# ECE_388_Schematic_v3.net
KiCad netlist of a schematic drawn in EAGLE
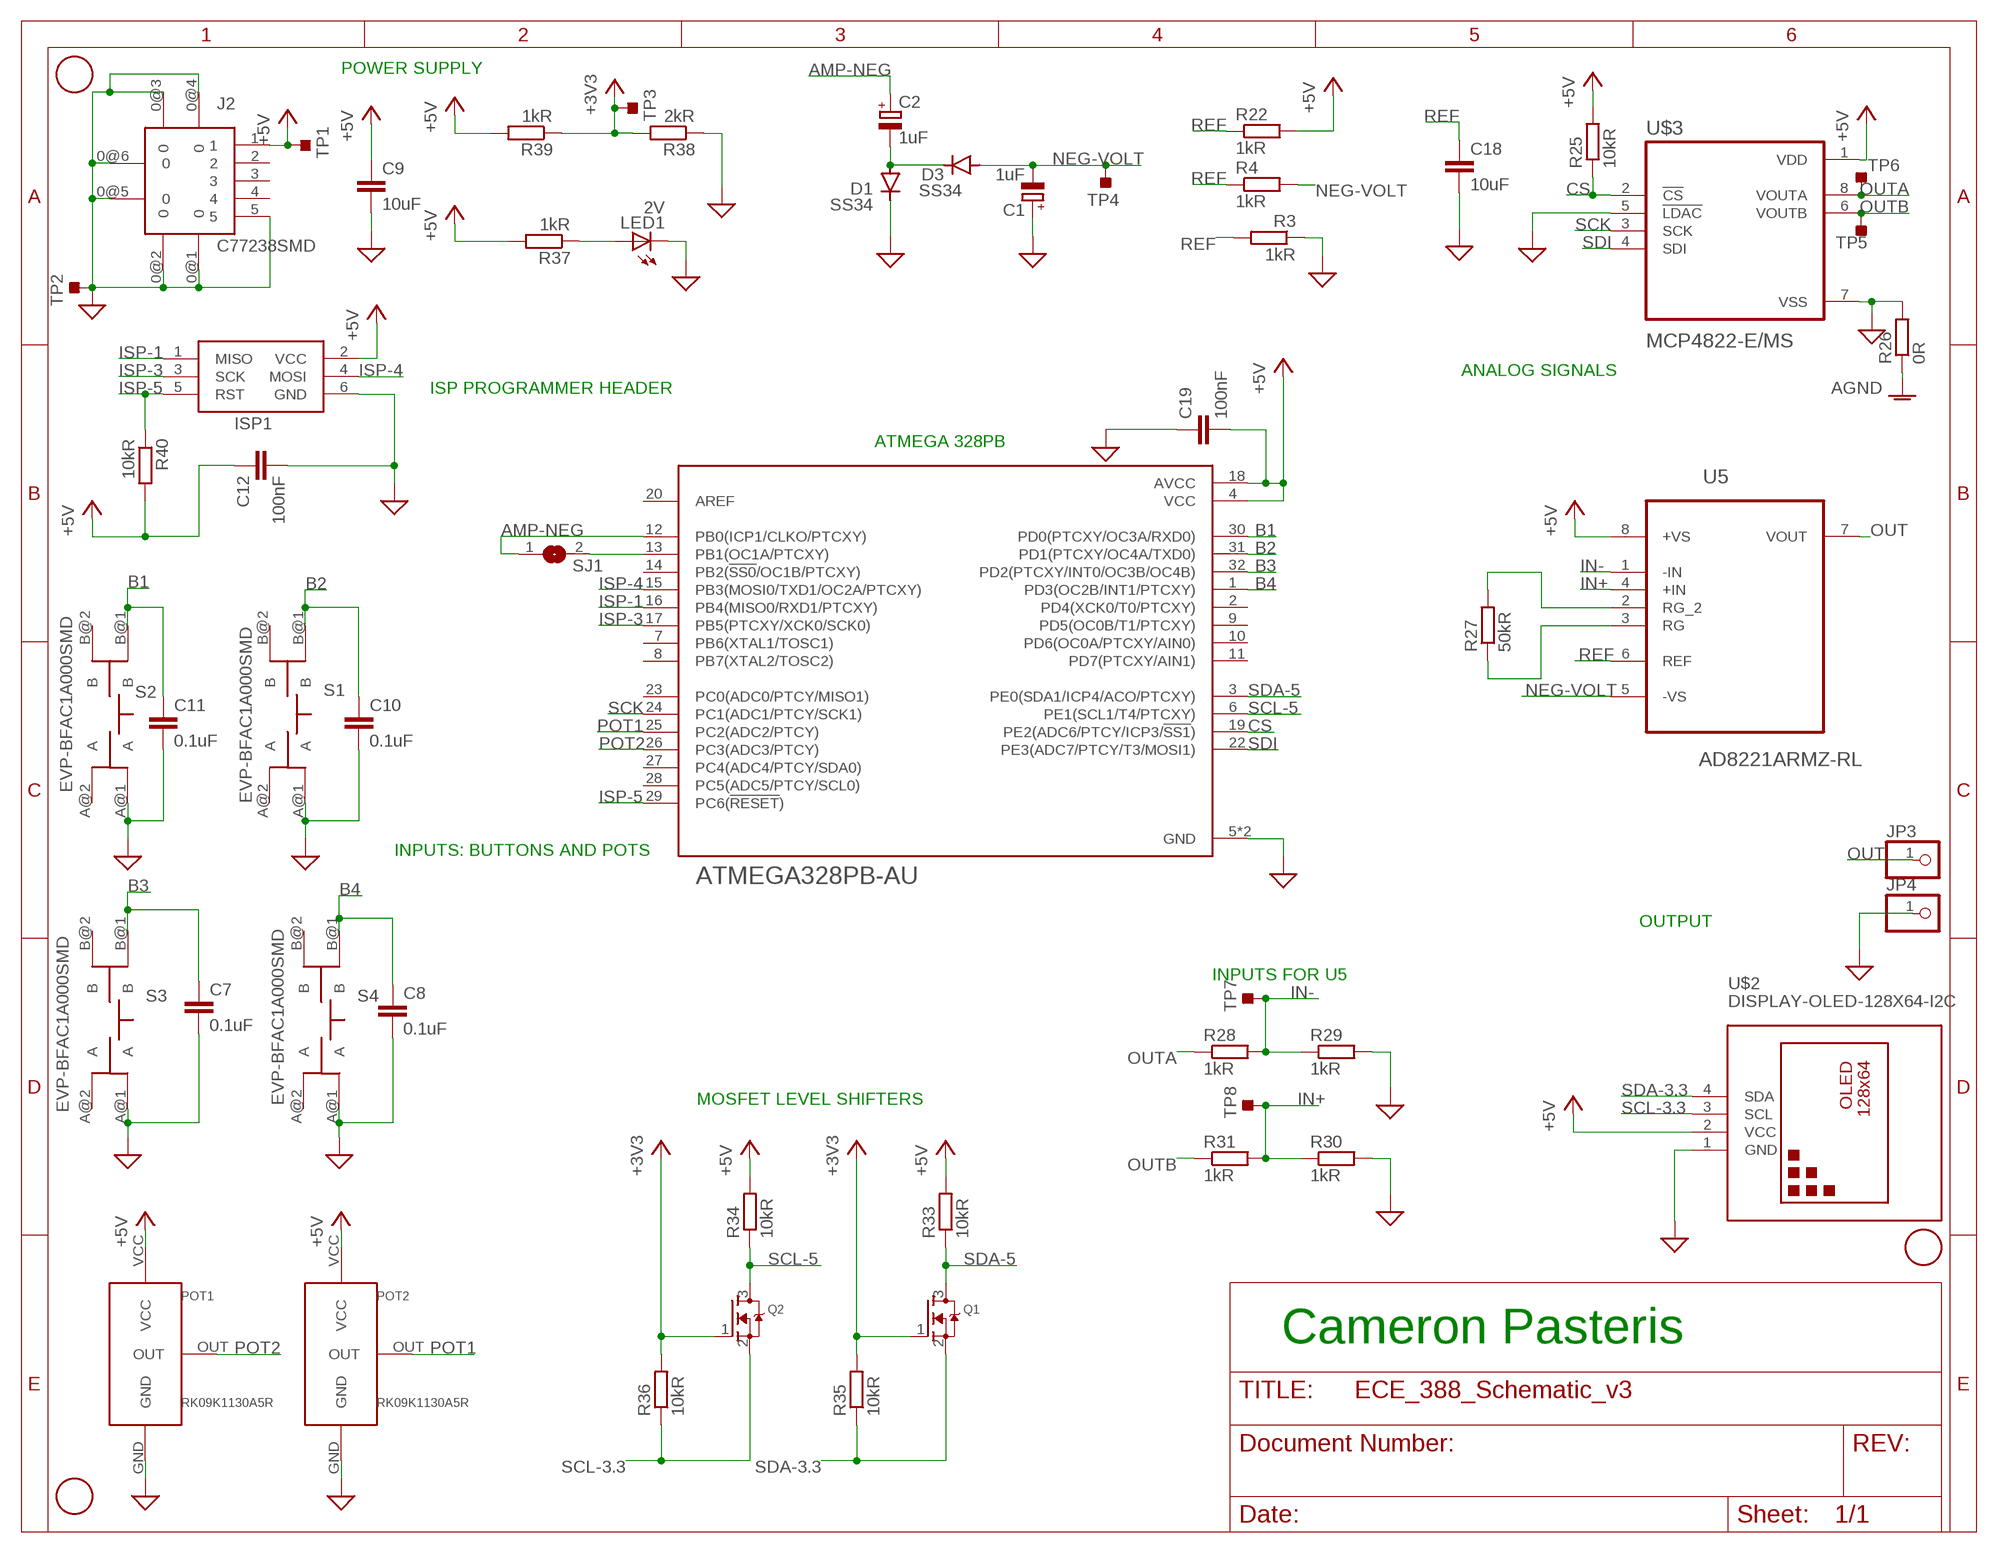
[diagram p0: schematic, sheet 1]

(export (version "E")
  (design (tool "Eeschema 10.0.6"))
  (components
    (comp (ref "C1")
      (value "1uF")
      (footprint "eagle-import:E2,5-6E")
      (libsource (lib "eagle-import") (part "CPOL-EUE2,5-6E"))
    )
    (comp (ref "C2")
      (value "1uF")
      (footprint "eagle-import:E2,5-6E")
      (libsource (lib "eagle-import") (part "CPOL-EUE2,5-6E"))
    )
    (comp (ref "C7")
      (value "0.1uF")
      (footprint "eagle-import:C0805")
      (libsource (lib "eagle-import") (part "C-EUC0805"))
    )
    (comp (ref "C8")
      (value "0.1uF")
      (footprint "eagle-import:C0805")
      (libsource (lib "eagle-import") (part "C-EUC0805"))
    )
    (comp (ref "C9")
      (value "10uF")
      (footprint "eagle-import:C0805")
      (libsource (lib "eagle-import") (part "C-EUC0805"))
    )
    (comp (ref "C10")
      (value "0.1uF")
      (footprint "eagle-import:C0805")
      (libsource (lib "eagle-import") (part "C-EUC0805"))
    )
    (comp (ref "C11")
      (value "0.1uF")
      (footprint "eagle-import:C0805")
      (libsource (lib "eagle-import") (part "C-EUC0805"))
    )
    (comp (ref "C12")
      (value "100nF")
      (footprint "eagle-import:C0805")
      (libsource (lib "eagle-import") (part "C-EUC0805"))
    )
    (comp (ref "C18")
      (value "10uF")
      (footprint "eagle-import:C0805")
      (libsource (lib "eagle-import") (part "C-EUC0805"))
    )
    (comp (ref "C19")
      (value "100nF")
      (footprint "eagle-import:C0805")
      (libsource (lib "eagle-import") (part "C-EUC0805"))
    )
    (comp (ref "D1")
      (value "SS34")
      (footprint "eagle-import:DO-214AC")
      (libsource (lib "eagle-import") (part "DIODE-DO-214AC"))
    )
    (comp (ref "D3")
      (value "SS34")
      (footprint "eagle-import:DO-214AC")
      (libsource (lib "eagle-import") (part "DIODE-DO-214AC"))
    )
    (comp (ref "F1")
      (value "FIDUCIAL")
      (footprint "eagle-import:FIDUCIAL_1MM")
      (libsource (lib "eagle-import") (part "FIDUCIAL"))
    )
    (comp (ref "F2")
      (value "FIDUCIAL")
      (footprint "eagle-import:FIDUCIAL_1MM")
      (libsource (lib "eagle-import") (part "FIDUCIAL"))
    )
    (comp (ref "F3")
      (value "FIDUCIAL")
      (footprint "eagle-import:FIDUCIAL_1MM")
      (libsource (lib "eagle-import") (part "FIDUCIAL"))
    )
    (comp (ref "ISP1")
      (value "AVRISP-6")
      (footprint "eagle-import:AVRISP")
      (libsource (lib "eagle-import") (part "AVRISP-6"))
    )
    (comp (ref "J2")
      (value "C77238SMD")
      (footprint "eagle-import:C77238")
      (libsource (lib "eagle-import") (part "C77238SMD"))
    )
    (comp (ref "JP3")
      (value "PINHD-1X1")
      (footprint "eagle-import:1X01")
      (libsource (lib "eagle-import") (part "PINHD-1X1"))
    )
    (comp (ref "JP4")
      (value "PINHD-1X1")
      (footprint "eagle-import:1X01")
      (libsource (lib "eagle-import") (part "PINHD-1X1"))
    )
    (comp (ref "LED1")
      (value "2V")
      (footprint "eagle-import:CHIP-LED0805")
      (libsource (lib "eagle-import") (part "LEDCHIP-LED0805"))
    )
    (comp (ref "POT1")
      (value "RK09K1130A5R")
      (footprint "eagle-import:RK09K1130A5R")
      (libsource (lib "eagle-import") (part "RK09K1130A5R"))
    )
    (comp (ref "POT2")
      (value "RK09K1130A5R")
      (footprint "eagle-import:RK09K1130A5R")
      (libsource (lib "eagle-import") (part "RK09K1130A5R"))
    )
    (comp (ref "Q1")
      (value "MOSFET-NREFLOW")
      (footprint "eagle-import:SOT23")
      (libsource (lib "eagle-import") (part "MOSFET-NREFLOW"))
    )
    (comp (ref "Q2")
      (value "MOSFET-NREFLOW")
      (footprint "eagle-import:SOT23")
      (libsource (lib "eagle-import") (part "MOSFET-NREFLOW"))
    )
    (comp (ref "R3")
      (value "1kR")
      (footprint "eagle-import:R0805")
      (libsource (lib "eagle-import") (part "R-EU_R0805"))
    )
    (comp (ref "R4")
      (value "1kR")
      (footprint "eagle-import:R0805")
      (libsource (lib "eagle-import") (part "R-EU_R0805"))
    )
    (comp (ref "R22")
      (value "1kR")
      (footprint "eagle-import:R0805")
      (libsource (lib "eagle-import") (part "R-EU_R0805"))
    )
    (comp (ref "R25")
      (value "10kR")
      (footprint "eagle-import:R0805")
      (libsource (lib "eagle-import") (part "R-EU_R0805"))
    )
    (comp (ref "R26")
      (value "0R")
      (footprint "eagle-import:R0805")
      (libsource (lib "eagle-import") (part "R-EU_R0805"))
    )
    (comp (ref "R27")
      (value "50kR")
      (footprint "eagle-import:R0805")
      (libsource (lib "eagle-import") (part "R-EU_R0805"))
    )
    (comp (ref "R28")
      (value "1kR")
      (footprint "eagle-import:R0805")
      (libsource (lib "eagle-import") (part "R-EU_R0805"))
    )
    (comp (ref "R29")
      (value "1kR")
      (footprint "eagle-import:R0805")
      (libsource (lib "eagle-import") (part "R-EU_R0805"))
    )
    (comp (ref "R30")
      (value "1kR")
      (footprint "eagle-import:R0805")
      (libsource (lib "eagle-import") (part "R-EU_R0805"))
    )
    (comp (ref "R31")
      (value "1kR")
      (footprint "eagle-import:R0805")
      (libsource (lib "eagle-import") (part "R-EU_R0805"))
    )
    (comp (ref "R33")
      (value "10kR")
      (footprint "eagle-import:R0805")
      (libsource (lib "eagle-import") (part "R-EU_R0805"))
    )
    (comp (ref "R34")
      (value "10kR")
      (footprint "eagle-import:R0805")
      (libsource (lib "eagle-import") (part "R-EU_R0805"))
    )
    (comp (ref "R35")
      (value "10kR")
      (footprint "eagle-import:R0805")
      (libsource (lib "eagle-import") (part "R-EU_R0805"))
    )
    (comp (ref "R36")
      (value "10kR")
      (footprint "eagle-import:R0805")
      (libsource (lib "eagle-import") (part "R-EU_R0805"))
    )
    (comp (ref "R37")
      (value "1kR")
      (footprint "eagle-import:R0805")
      (libsource (lib "eagle-import") (part "R-EU_R0805"))
    )
    (comp (ref "R38")
      (value "2kR")
      (footprint "eagle-import:R0805")
      (libsource (lib "eagle-import") (part "R-EU_R0805"))
    )
    (comp (ref "R39")
      (value "1kR")
      (footprint "eagle-import:R0805")
      (libsource (lib "eagle-import") (part "R-EU_R0805"))
    )
    (comp (ref "R40")
      (value "10kR")
      (footprint "eagle-import:R0805")
      (libsource (lib "eagle-import") (part "R-EU_R0805"))
    )
    (comp (ref "S1")
      (value "EVP-BFAC1A000SMD")
      (footprint "eagle-import:EVP-BFAC1A000")
      (libsource (lib "eagle-import") (part "EVP-BFAC1A000SMD"))
    )
    (comp (ref "S2")
      (value "EVP-BFAC1A000SMD")
      (footprint "eagle-import:EVP-BFAC1A000")
      (libsource (lib "eagle-import") (part "EVP-BFAC1A000SMD"))
    )
    (comp (ref "S3")
      (value "EVP-BFAC1A000SMD")
      (footprint "eagle-import:EVP-BFAC1A000")
      (libsource (lib "eagle-import") (part "EVP-BFAC1A000SMD"))
    )
    (comp (ref "S4")
      (value "EVP-BFAC1A000SMD")
      (footprint "eagle-import:EVP-BFAC1A000")
      (libsource (lib "eagle-import") (part "EVP-BFAC1A000SMD"))
    )
    (comp (ref "SJ1") (value "SJ") (footprint "eagle-import:SJ") (libsource (lib "eagle-import") (part "SJ")))
    (comp (ref "TP1")
      (value "TESTPOINT_TPS-PAD-036")
      (footprint "eagle-import:TESTPOINT_PAD-036")
      (libsource (lib "eagle-import") (part "TESTPOINT_TPS-PAD-036"))
    )
    (comp (ref "TP2")
      (value "TESTPOINT_TPS-PAD-036")
      (footprint "eagle-import:TESTPOINT_PAD-036")
      (libsource (lib "eagle-import") (part "TESTPOINT_TPS-PAD-036"))
    )
    (comp (ref "TP3")
      (value "TESTPOINT_TPS-PAD-036")
      (footprint "eagle-import:TESTPOINT_PAD-036")
      (libsource (lib "eagle-import") (part "TESTPOINT_TPS-PAD-036"))
    )
    (comp (ref "TP4")
      (value "TESTPOINT_TPS-PAD-036")
      (footprint "eagle-import:TESTPOINT_PAD-036")
      (libsource (lib "eagle-import") (part "TESTPOINT_TPS-PAD-036"))
    )
    (comp (ref "TP5")
      (value "TESTPOINT_TPS-PAD-036")
      (footprint "eagle-import:TESTPOINT_PAD-036")
      (libsource (lib "eagle-import") (part "TESTPOINT_TPS-PAD-036"))
    )
    (comp (ref "TP6")
      (value "TESTPOINT_TPS-PAD-036")
      (footprint "eagle-import:TESTPOINT_PAD-036")
      (libsource (lib "eagle-import") (part "TESTPOINT_TPS-PAD-036"))
    )
    (comp (ref "TP7")
      (value "TESTPOINT_TPS-PAD-036")
      (footprint "eagle-import:TESTPOINT_PAD-036")
      (libsource (lib "eagle-import") (part "TESTPOINT_TPS-PAD-036"))
    )
    (comp (ref "TP8")
      (value "TESTPOINT_TPS-PAD-036")
      (footprint "eagle-import:TESTPOINT_PAD-036")
      (libsource (lib "eagle-import") (part "TESTPOINT_TPS-PAD-036"))
    )
    (comp (ref "U$2")
      (value "DISPLAY-OLED-128X64-I2C")
      (footprint "eagle-import:DISPLAY-OLED-128X64-I2C")
      (libsource (lib "eagle-import") (part "DISPLAY-OLED-128X64-I2C"))
    )
    (comp (ref "U$3")
      (value "MCP4822-E/MS")
      (footprint "eagle-import:SOP65P490X110-8N")
      (fields (field (name "MF") "Microchip"))
      (libsource (lib "eagle-import") (part "MCP4822-E/MS"))
    )
    (comp (ref "U1")
      (value "ATMEGA328PB-AU")
      (footprint "eagle-import:QFP80P900X900X120-32N")
      (fields (field (name "MF") "Microchip Technology / Atmel"))
      (libsource (lib "eagle-import") (part "ATMEGA328PB-AU"))
    )
    (comp (ref "U5")
      (value "AD8221ARMZ-RL")
      (footprint "eagle-import:SOP65P490X110-8N")
      (fields (field (name "MF") "Analog Devices"))
      (libsource (lib "eagle-import") (part "AD8221ARMZ-RL"))
    )
  )
  (nets
    (net (code "1") (name "+3V3") (class "Default")
      (node (ref "Q1") (pin "1") (pinfunction "G_1") (pintype "bidirectional"))
      (node (ref "Q2") (pin "1") (pinfunction "G_1") (pintype "bidirectional"))
      (node (ref "R35") (pin "2") (pinfunction "2_2") (pintype "passive"))
      (node (ref "R36") (pin "2") (pinfunction "2_2") (pintype "passive"))
      (node (ref "R38") (pin "2") (pinfunction "2_2") (pintype "passive"))
      (node (ref "R39") (pin "1") (pinfunction "1_1") (pintype "passive"))
      (node (ref "TP3") (pin "1") (pinfunction "TP_1") (pintype "passive"))
    )
    (net (code "2") (name "+5V") (class "Default")
      (node (ref "C12") (pin "1") (pinfunction "1_1") (pintype "passive"))
      (node (ref "C19") (pin "2") (pinfunction "2_2") (pintype "passive"))
      (node (ref "C9") (pin "1") (pinfunction "1_1") (pintype "passive"))
      (node (ref "ISP1") (pin "2") (pinfunction "VCC_2") (pintype "power_in"))
      (node (ref "J2") (pin "1") (pinfunction "1_1") (pintype "power_in"))
      (node (ref "POT1") (pin "VCC") (pinfunction "VCC_VCC") (pintype "bidirectional"))
      (node (ref "POT2") (pin "VCC") (pinfunction "VCC_VCC") (pintype "bidirectional"))
      (node (ref "R22") (pin "2") (pinfunction "2_2") (pintype "passive"))
      (node (ref "R25") (pin "2") (pinfunction "2_2") (pintype "passive"))
      (node (ref "R33") (pin "2") (pinfunction "2_2") (pintype "passive"))
      (node (ref "R34") (pin "2") (pinfunction "2_2") (pintype "passive"))
      (node (ref "R37") (pin "2") (pinfunction "2_2") (pintype "passive"))
      (node (ref "R39") (pin "2") (pinfunction "2_2") (pintype "passive"))
      (node (ref "R40") (pin "2") (pinfunction "2_2") (pintype "passive"))
      (node (ref "TP1") (pin "1") (pinfunction "TP_1") (pintype "passive"))
      (node (ref "U$2") (pin "2") (pinfunction "VCC_2") (pintype "power_in"))
      (node (ref "U$3") (pin "1") (pinfunction "VDD_1") (pintype "power_in"))
      (node (ref "U1") (pin "18") (pinfunction "AVCC_18") (pintype "power_in"))
      (node (ref "U1") (pin "4") (pinfunction "VCC_4") (pintype "power_in"))
      (node (ref "U5") (pin "8") (pinfunction "+VS_8") (pintype "power_in"))
    )
    (net (code "3") (name "/AMP-NEG") (class "Default")
      (node (ref "C2") (pin "+") (pinfunction "+_+") (pintype "passive"))
      (node (ref "SJ1") (pin "1") (pinfunction "1_1") (pintype "passive"))
      (node (ref "U1") (pin "12") (pinfunction "PB0(ICP1/CLKO/PTCXY)_12") (pintype "bidirectional"))
    )
    (net (code "4") (name "/B1") (class "Default")
      (node (ref "C11") (pin "1") (pinfunction "1_1") (pintype "passive"))
      (node (ref "S2") (pin "B@1") (pinfunction "B_B@1") (pintype "bidirectional"))
      (node (ref "U1") (pin "30") (pinfunction "PD0(PTCXY/OC3A/RXD0)_30") (pintype "bidirectional"))
    )
    (net (code "5") (name "/B2") (class "Default")
      (node (ref "C10") (pin "1") (pinfunction "1_1") (pintype "passive"))
      (node (ref "S1") (pin "B@1") (pinfunction "B_B@1") (pintype "bidirectional"))
      (node (ref "U1") (pin "31") (pinfunction "PD1(PTCXY/OC4A/TXD0)_31") (pintype "bidirectional"))
    )
    (net (code "6") (name "/B3") (class "Default")
      (node (ref "C7") (pin "1") (pinfunction "1_1") (pintype "passive"))
      (node (ref "S3") (pin "B@1") (pinfunction "B_B@1") (pintype "bidirectional"))
      (node (ref "U1") (pin "32") (pinfunction "PD2(PTCXY/INT0/OC3B/OC4B)_32") (pintype "bidirectional"))
    )
    (net (code "7") (name "/B4") (class "Default")
      (node (ref "C8") (pin "1") (pinfunction "1_1") (pintype "passive"))
      (node (ref "S4") (pin "B@1") (pinfunction "B_B@1") (pintype "bidirectional"))
      (node (ref "U1") (pin "1") (pinfunction "PD3(OC2B/INT1/PTCXY)_1") (pintype "bidirectional"))
    )
    (net (code "8") (name "/CS") (class "Default")
      (node (ref "R25") (pin "1") (pinfunction "1_1") (pintype "passive"))
      (node (ref "U$3") (pin "2") (pinfunction "~{CS}_2") (pintype "input"))
      (node (ref "U1") (pin "19") (pinfunction "PE2(ADC6/PTCY/ICP3/~{SS1})_19") (pintype "bidirectional"))
    )
    (net (code "9") (name "/IN+") (class "Default")
      (node (ref "R30") (pin "1") (pinfunction "1_1") (pintype "passive"))
      (node (ref "R31") (pin "2") (pinfunction "2_2") (pintype "passive"))
      (node (ref "TP8") (pin "1") (pinfunction "TP_1") (pintype "passive"))
      (node (ref "U5") (pin "4") (pinfunction "+IN_4") (pintype "input"))
    )
    (net (code "10") (name "/IN-") (class "Default")
      (node (ref "R28") (pin "2") (pinfunction "2_2") (pintype "passive"))
      (node (ref "R29") (pin "1") (pinfunction "1_1") (pintype "passive"))
      (node (ref "TP7") (pin "1") (pinfunction "TP_1") (pintype "passive"))
      (node (ref "U5") (pin "1") (pinfunction "-IN_1") (pintype "input"))
    )
    (net (code "11") (name "/ISP-1") (class "Default")
      (node (ref "ISP1") (pin "1") (pinfunction "MISO_1") (pintype "input"))
      (node (ref "U1") (pin "16") (pinfunction "PB4(MISO0/RXD1/PTCXY)_16") (pintype "bidirectional"))
    )
    (net (code "12") (name "/ISP-3") (class "Default")
      (node (ref "ISP1") (pin "3") (pinfunction "SCK_3") (pintype "output"))
      (node (ref "U1") (pin "17") (pinfunction "PB5(PTCXY/XCK0/SCK0)_17") (pintype "bidirectional"))
    )
    (net (code "13") (name "/ISP-4") (class "Default")
      (node (ref "ISP1") (pin "4") (pinfunction "MOSI_4") (pintype "output"))
      (node (ref "U1") (pin "15") (pinfunction "PB3(MOSI0/TXD1/OC2A/PTCXY)_15") (pintype "bidirectional"))
    )
    (net (code "14") (name "/ISP-5") (class "Default")
      (node (ref "ISP1") (pin "5") (pinfunction "RST_5") (pintype "output"))
      (node (ref "R40") (pin "1") (pinfunction "1_1") (pintype "passive"))
      (node (ref "U1") (pin "29") (pinfunction "PC6(~{RESET})_29") (pintype "bidirectional"))
    )
    (net (code "15") (name "/NEG-VOLT") (class "Default")
      (node (ref "C1") (pin "-") (pinfunction "-_-") (pintype "passive"))
      (node (ref "D3") (pin "A") (pinfunction "A_A") (pintype "passive"))
      (node (ref "R4") (pin "2") (pinfunction "2_2") (pintype "passive"))
      (node (ref "TP4") (pin "1") (pinfunction "TP_1") (pintype "passive"))
      (node (ref "U5") (pin "5") (pinfunction "-VS_5") (pintype "power_in"))
    )
    (net (code "16") (name "/OUT") (class "Default")
      (node (ref "JP3") (pin "1") (pinfunction "1_1") (pintype "passive"))
      (node (ref "U5") (pin "7") (pinfunction "VOUT_7") (pintype "output"))
    )
    (net (code "17") (name "/OUTA") (class "Default")
      (node (ref "R28") (pin "1") (pinfunction "1_1") (pintype "passive"))
      (node (ref "TP6") (pin "1") (pinfunction "TP_1") (pintype "passive"))
      (node (ref "U$3") (pin "8") (pinfunction "VOUTA_8") (pintype "output"))
    )
    (net (code "18") (name "/OUTB") (class "Default")
      (node (ref "R31") (pin "1") (pinfunction "1_1") (pintype "passive"))
      (node (ref "TP5") (pin "1") (pinfunction "TP_1") (pintype "passive"))
      (node (ref "U$3") (pin "6") (pinfunction "VOUTB_6") (pintype "output"))
    )
    (net (code "19") (name "/POT1") (class "Default")
      (node (ref "POT2") (pin "OUT") (pinfunction "OUT_OUT") (pintype "bidirectional"))
      (node (ref "U1") (pin "25") (pinfunction "PC2(ADC2/PTCY)_25") (pintype "bidirectional"))
    )
    (net (code "20") (name "/POT2") (class "Default")
      (node (ref "POT1") (pin "OUT") (pinfunction "OUT_OUT") (pintype "bidirectional"))
      (node (ref "U1") (pin "26") (pinfunction "PC3(ADC3/PTCY)_26") (pintype "bidirectional"))
    )
    (net (code "21") (name "/REF") (class "Default")
      (node (ref "C18") (pin "1") (pinfunction "1_1") (pintype "passive"))
      (node (ref "R22") (pin "1") (pinfunction "1_1") (pintype "passive"))
      (node (ref "R3") (pin "2") (pinfunction "2_2") (pintype "passive"))
      (node (ref "R4") (pin "1") (pinfunction "1_1") (pintype "passive"))
      (node (ref "U5") (pin "6") (pinfunction "REF_6") (pintype "passive"))
    )
    (net (code "22") (name "/SCK") (class "Default")
      (node (ref "U$3") (pin "3") (pinfunction "SCK_3") (pintype "input"))
      (node (ref "U1") (pin "24") (pinfunction "PC1(ADC1/PTCY/SCK1)_24") (pintype "bidirectional"))
    )
    (net (code "23") (name "/SCL-3.3") (class "Default")
      (node (ref "Q2") (pin "2") (pinfunction "S_2") (pintype "bidirectional"))
      (node (ref "R36") (pin "1") (pinfunction "1_1") (pintype "passive"))
      (node (ref "U$2") (pin "3") (pinfunction "SCL_3") (pintype "bidirectional"))
    )
    (net (code "24") (name "/SCL-5") (class "Default")
      (node (ref "Q2") (pin "3") (pinfunction "D_3") (pintype "bidirectional"))
      (node (ref "R34") (pin "1") (pinfunction "1_1") (pintype "passive"))
      (node (ref "U1") (pin "6") (pinfunction "PE1(SCL1/T4/PTCXY)_6") (pintype "bidirectional"))
    )
    (net (code "25") (name "/SDA-3.3") (class "Default")
      (node (ref "Q1") (pin "2") (pinfunction "S_2") (pintype "bidirectional"))
      (node (ref "R35") (pin "1") (pinfunction "1_1") (pintype "passive"))
      (node (ref "U$2") (pin "4") (pinfunction "SDA_4") (pintype "bidirectional"))
    )
    (net (code "26") (name "/SDA-5") (class "Default")
      (node (ref "Q1") (pin "3") (pinfunction "D_3") (pintype "bidirectional"))
      (node (ref "R33") (pin "1") (pinfunction "1_1") (pintype "passive"))
      (node (ref "U1") (pin "3") (pinfunction "PE0(SDA1/ICP4/ACO/PTCXY)_3") (pintype "bidirectional"))
    )
    (net (code "27") (name "/SDI") (class "Default")
      (node (ref "U$3") (pin "4") (pinfunction "SDI_4") (pintype "input"))
      (node (ref "U1") (pin "22") (pinfunction "PE3(ADC7/PTCY/T3/MOSI1)_22") (pintype "bidirectional"))
    )
    (net (code "28") (name "AGND") (class "Default")
      (node (ref "R26") (pin "1") (pinfunction "1_1") (pintype "passive"))
    )
    (net (code "29") (name "Net-(C2-Pad-)") (class "Default")
      (node (ref "C2") (pin "-") (pinfunction "-_-") (pintype "passive"))
      (node (ref "D1") (pin "A") (pinfunction "A_A") (pintype "passive"))
      (node (ref "D3") (pin "C") (pinfunction "C_C") (pintype "passive"))
    )
    (net (code "30") (name "Net-(LED1-PadA)") (class "Default")
      (node (ref "LED1") (pin "A") (pinfunction "A_A") (pintype "passive"))
      (node (ref "R37") (pin "1") (pinfunction "1_1") (pintype "passive"))
    )
    (net (code "31") (name "Net-(U1-PB1(OC1A{slash}PTCXY))") (class "Default")
      (node (ref "SJ1") (pin "2") (pinfunction "2_2") (pintype "passive"))
      (node (ref "U1") (pin "13") (pinfunction "PB1(OC1A/PTCXY)_13") (pintype "bidirectional"))
    )
    (net (code "32") (name "Net-(U5-RG)") (class "Default")
      (node (ref "R27") (pin "1") (pinfunction "1_1") (pintype "passive"))
      (node (ref "U5") (pin "3") (pinfunction "RG_3") (pintype "input"))
    )
    (net (code "33") (name "Net-(U5-RG_2)") (class "Default")
      (node (ref "R27") (pin "2") (pinfunction "2_2") (pintype "passive"))
      (node (ref "U5") (pin "2") (pinfunction "RG_2_2") (pintype "input"))
    )
    (net (code "34") (name "SUP") (class "Default")
      (node (ref "C1") (pin "+") (pinfunction "+_+") (pintype "passive"))
      (node (ref "C10") (pin "2") (pinfunction "2_2") (pintype "passive"))
      (node (ref "C11") (pin "2") (pinfunction "2_2") (pintype "passive"))
      (node (ref "C12") (pin "2") (pinfunction "2_2") (pintype "passive"))
      (node (ref "C18") (pin "2") (pinfunction "2_2") (pintype "passive"))
      (node (ref "C19") (pin "1") (pinfunction "1_1") (pintype "passive"))
      (node (ref "C7") (pin "2") (pinfunction "2_2") (pintype "passive"))
      (node (ref "C8") (pin "2") (pinfunction "2_2") (pintype "passive"))
      (node (ref "C9") (pin "2") (pinfunction "2_2") (pintype "passive"))
      (node (ref "D1") (pin "C") (pinfunction "C_C") (pintype "passive"))
      (node (ref "ISP1") (pin "6") (pinfunction "GND_6") (pintype "power_in"))
      (node (ref "J2") (pin "0@1") (pinfunction "0_0@1") (pintype "bidirectional"))
      (node (ref "J2") (pin "0@2") (pinfunction "0_0@2") (pintype "bidirectional"))
      (node (ref "J2") (pin "0@3") (pinfunction "0_0@3") (pintype "bidirectional"))
      (node (ref "J2") (pin "0@4") (pinfunction "0_0@4") (pintype "bidirectional"))
      (node (ref "J2") (pin "0@5") (pinfunction "0_0@5") (pintype "bidirectional"))
      (node (ref "J2") (pin "0@6") (pinfunction "0_0@6") (pintype "bidirectional"))
      (node (ref "J2") (pin "5") (pinfunction "5_5") (pintype "power_in"))
      (node (ref "JP4") (pin "1") (pinfunction "1_1") (pintype "passive"))
      (node (ref "LED1") (pin "C") (pinfunction "C_C") (pintype "passive"))
      (node (ref "POT1") (pin "GND") (pinfunction "GND_GND") (pintype "bidirectional"))
      (node (ref "POT2") (pin "GND") (pinfunction "GND_GND") (pintype "bidirectional"))
      (node (ref "R26") (pin "2") (pinfunction "2_2") (pintype "passive"))
      (node (ref "R29") (pin "2") (pinfunction "2_2") (pintype "passive"))
      (node (ref "R3") (pin "1") (pinfunction "1_1") (pintype "passive"))
      (node (ref "R30") (pin "2") (pinfunction "2_2") (pintype "passive"))
      (node (ref "R38") (pin "1") (pinfunction "1_1") (pintype "passive"))
      (node (ref "S1") (pin "A@1") (pinfunction "A_A@1") (pintype "bidirectional"))
      (node (ref "S2") (pin "A@1") (pinfunction "A_A@1") (pintype "bidirectional"))
      (node (ref "S3") (pin "A@1") (pinfunction "A_A@1") (pintype "bidirectional"))
      (node (ref "S4") (pin "A@1") (pinfunction "A_A@1") (pintype "bidirectional"))
      (node (ref "TP2") (pin "1") (pinfunction "TP_1") (pintype "passive"))
      (node (ref "U$2") (pin "1") (pinfunction "GND_1") (pintype "power_in"))
      (node (ref "U$3") (pin "5") (pinfunction "~{LDAC}_5") (pintype "input"))
      (node (ref "U$3") (pin "7") (pinfunction "VSS_7") (pintype "power_in"))
      (node (ref "U1") (pin "21") (pinfunction "GND_21") (pintype "power_in"))
      (node (ref "U1") (pin "5") (pinfunction "GND_5") (pintype "power_in"))
    )
    (net (code "35") (name "unconnected-(J2-Pad2)") (class "Default")
      (node (ref "J2") (pin "2") (pinfunction "2_2") (pintype "bidirectional"))
    )
    (net (code "36") (name "unconnected-(J2-Pad3)") (class "Default")
      (node (ref "J2") (pin "3") (pinfunction "3_3") (pintype "bidirectional"))
    )
    (net (code "37") (name "unconnected-(J2-Pad4)") (class "Default")
      (node (ref "J2") (pin "4") (pinfunction "4_4") (pintype "bidirectional"))
    )
    (net (code "38") (name "unconnected-(S1-A-PadA@2)") (class "Default")
      (node (ref "S1") (pin "A@2") (pinfunction "A_A@2") (pintype "bidirectional"))
    )
    (net (code "39") (name "unconnected-(S1-B-PadB@2)") (class "Default")
      (node (ref "S1") (pin "B@2") (pinfunction "B_B@2") (pintype "bidirectional"))
    )
    (net (code "40") (name "unconnected-(S2-A-PadA@2)") (class "Default")
      (node (ref "S2") (pin "A@2") (pinfunction "A_A@2") (pintype "bidirectional"))
    )
    (net (code "41") (name "unconnected-(S2-B-PadB@2)") (class "Default")
      (node (ref "S2") (pin "B@2") (pinfunction "B_B@2") (pintype "bidirectional"))
    )
    (net (code "42") (name "unconnected-(S3-A-PadA@2)") (class "Default")
      (node (ref "S3") (pin "A@2") (pinfunction "A_A@2") (pintype "bidirectional"))
    )
    (net (code "43") (name "unconnected-(S3-B-PadB@2)") (class "Default")
      (node (ref "S3") (pin "B@2") (pinfunction "B_B@2") (pintype "bidirectional"))
    )
    (net (code "44") (name "unconnected-(S4-A-PadA@2)") (class "Default")
      (node (ref "S4") (pin "A@2") (pinfunction "A_A@2") (pintype "bidirectional"))
    )
    (net (code "45") (name "unconnected-(S4-B-PadB@2)") (class "Default")
      (node (ref "S4") (pin "B@2") (pinfunction "B_B@2") (pintype "bidirectional"))
    )
    (net (code "46") (name "unconnected-(U1-AREF-Pad20)") (class "Default")
      (node (ref "U1") (pin "20") (pinfunction "AREF_20") (pintype "input"))
    )
    (net (code "47") (name "unconnected-(U1-PB2(~{SS0}{slash}OC1B{slash}PTCXY)-Pad14)") (class "Default")
      (node (ref "U1") (pin "14") (pinfunction "PB2(~{SS0}/OC1B/PTCXY)_14") (pintype "bidirectional"))
    )
    (net (code "48") (name "unconnected-(U1-PB6(XTAL1{slash}TOSC1)-Pad7)") (class "Default")
      (node (ref "U1") (pin "7") (pinfunction "PB6(XTAL1/TOSC1)_7") (pintype "bidirectional"))
    )
    (net (code "49") (name "unconnected-(U1-PB7(XTAL2{slash}TOSC2)-Pad8)") (class "Default")
      (node (ref "U1") (pin "8") (pinfunction "PB7(XTAL2/TOSC2)_8") (pintype "bidirectional"))
    )
    (net (code "50") (name "unconnected-(U1-PC0(ADC0{slash}PTCY{slash}MISO1)-Pad23)") (class "Default")
      (node (ref "U1") (pin "23") (pinfunction "PC0(ADC0/PTCY/MISO1)_23") (pintype "bidirectional"))
    )
    (net (code "51") (name "unconnected-(U1-PC4(ADC4{slash}PTCY{slash}SDA0)-Pad27)") (class "Default")
      (node (ref "U1") (pin "27") (pinfunction "PC4(ADC4/PTCY/SDA0)_27") (pintype "bidirectional"))
    )
    (net (code "52") (name "unconnected-(U1-PC5(ADC5{slash}PTCY{slash}SCL0)-Pad28)") (class "Default")
      (node (ref "U1") (pin "28") (pinfunction "PC5(ADC5/PTCY/SCL0)_28") (pintype "bidirectional"))
    )
    (net (code "53") (name "unconnected-(U1-PD4(XCK0{slash}T0{slash}PTCXY)-Pad2)") (class "Default")
      (node (ref "U1") (pin "2") (pinfunction "PD4(XCK0/T0/PTCXY)_2") (pintype "bidirectional"))
    )
    (net (code "54") (name "unconnected-(U1-PD5(OC0B{slash}T1{slash}PTCXY)-Pad9)") (class "Default")
      (node (ref "U1") (pin "9") (pinfunction "PD5(OC0B/T1/PTCXY)_9") (pintype "bidirectional"))
    )
    (net (code "55") (name "unconnected-(U1-PD6(OC0A{slash}PTCXY{slash}AIN0)-Pad10)") (class "Default")
      (node (ref "U1") (pin "10") (pinfunction "PD6(OC0A/PTCXY/AIN0)_10") (pintype "bidirectional"))
    )
    (net (code "56") (name "unconnected-(U1-PD7(PTCXY{slash}AIN1)-Pad11)") (class "Default")
      (node (ref "U1") (pin "11") (pinfunction "PD7(PTCXY/AIN1)_11") (pintype "bidirectional"))
    )
  )
)
